# Top_Board_Boundary_Ref.net
KiCad netlist of a schematic drawn in EAGLE
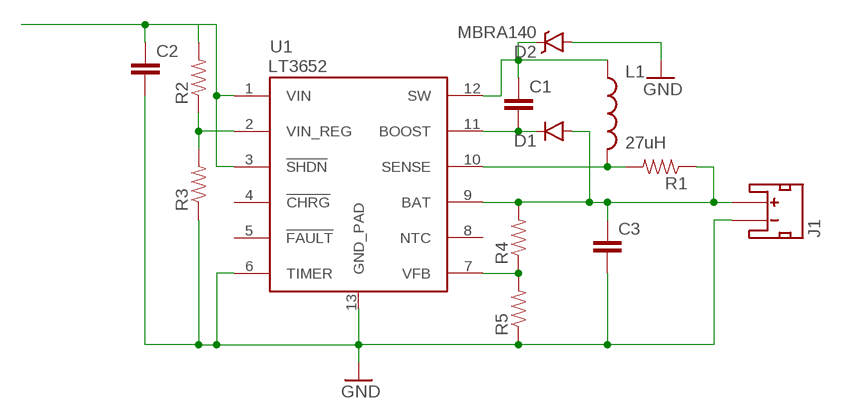
[diagram p0: schematic, sheet 1]

(export (version "E")
  (design (tool "Eeschema 10.0.6"))
  (components
    (comp (ref "C1")
      (value "CAP0805")
      (footprint "eagle-import:0805")
      (libsource (lib "eagle-import") (part "CAP0805"))
    )
    (comp (ref "C2")
      (value "CAP0805")
      (footprint "eagle-import:0805")
      (libsource (lib "eagle-import") (part "CAP0805"))
    )
    (comp (ref "C3")
      (value "CAP0805")
      (footprint "eagle-import:0805")
      (libsource (lib "eagle-import") (part "CAP0805"))
    )
    (comp (ref "D1")
      (value "DIODESMA")
      (footprint "eagle-import:SMA-DIODE")
      (libsource (lib "eagle-import") (part "DIODESMA"))
    )
    (comp (ref "D2")
      (value "MBRA140")
      (footprint "eagle-import:SMA-DIODE")
      (libsource (lib "eagle-import") (part "DIODE-SCHOTTKY-MBRA140"))
    )
    (comp (ref "J1")
      (value "JST_2MM_MALE")
      (footprint "eagle-import:JST-2-SMD")
      (libsource (lib "eagle-import") (part "JST_2MM_MALE"))
    )
    (comp (ref "L1")
      (value "27uH")
      (footprint "eagle-import:INDUCTOR_SDR1307")
      (libsource (lib "eagle-import") (part "INDUCTORSDR13-7-270ML"))
    )
    (comp (ref "R1")
      (value "RESISTOR0805-RES")
      (footprint "eagle-import:0805")
      (libsource (lib "eagle-import") (part "RESISTOR0805-RES"))
    )
    (comp (ref "R2")
      (value "RESISTOR0805-RES")
      (footprint "eagle-import:0805")
      (libsource (lib "eagle-import") (part "RESISTOR0805-RES"))
    )
    (comp (ref "R3")
      (value "RESISTOR0805-RES")
      (footprint "eagle-import:0805")
      (libsource (lib "eagle-import") (part "RESISTOR0805-RES"))
    )
    (comp (ref "R4")
      (value "RESISTOR0805-RES")
      (footprint "eagle-import:0805")
      (libsource (lib "eagle-import") (part "RESISTOR0805-RES"))
    )
    (comp (ref "R5")
      (value "RESISTOR0805-RES")
      (footprint "eagle-import:0805")
      (libsource (lib "eagle-import") (part "RESISTOR0805-RES"))
    )
    (comp (ref "U1")
      (value "LT3652")
      (footprint "eagle-import:MSOP-12_GND")
      (libsource (lib "eagle-import") (part "LT3652"))
    )
  )
  (nets
    (net (code "1") (name "GND") (class "Default")
      (node (ref "C2") (pin "2") (pinfunction "2_2") (pintype "passive"))
      (node (ref "C3") (pin "2") (pinfunction "2_2") (pintype "passive"))
      (node (ref "D2") (pin "A") (pinfunction "A_A") (pintype "passive"))
      (node (ref "J1") (pin "1") (pinfunction "-_1") (pintype "bidirectional"))
      (node (ref "R3") (pin "1") (pinfunction "1_1") (pintype "passive"))
      (node (ref "R5") (pin "1") (pinfunction "1_1") (pintype "passive"))
      (node (ref "U1") (pin "13") (pinfunction "GND_PAD_13") (pintype "bidirectional"))
      (node (ref "U1") (pin "6") (pinfunction "TIMER_6") (pintype "bidirectional"))
    )
    (net (code "2") (name "Net-(J1-+)") (class "Default")
      (node (ref "C3") (pin "1") (pinfunction "1_1") (pintype "passive"))
      (node (ref "D1") (pin "A") (pinfunction "A_A") (pintype "passive"))
      (node (ref "J1") (pin "2") (pinfunction "+_2") (pintype "bidirectional"))
      (node (ref "R1") (pin "1") (pinfunction "1_1") (pintype "passive"))
      (node (ref "R4") (pin "2") (pinfunction "2_2") (pintype "passive"))
      (node (ref "U1") (pin "9") (pinfunction "BAT_9") (pintype "bidirectional"))
    )
    (net (code "3") (name "Net-(L1-1)") (class "Default")
      (node (ref "C1") (pin "1") (pinfunction "1_1") (pintype "passive"))
      (node (ref "D2") (pin "C") (pinfunction "C_C") (pintype "passive"))
      (node (ref "L1") (pin "P$1") (pinfunction "1_P$1") (pintype "passive"))
      (node (ref "U1") (pin "12") (pinfunction "SW_12") (pintype "bidirectional"))
    )
    (net (code "4") (name "Net-(L1-2)") (class "Default")
      (node (ref "L1") (pin "P$2") (pinfunction "2_P$2") (pintype "passive"))
      (node (ref "R1") (pin "2") (pinfunction "2_2") (pintype "passive"))
      (node (ref "U1") (pin "10") (pinfunction "SENSE_10") (pintype "bidirectional"))
    )
    (net (code "5") (name "Net-(U1-BOOST)") (class "Default")
      (node (ref "C1") (pin "2") (pinfunction "2_2") (pintype "passive"))
      (node (ref "D1") (pin "C") (pinfunction "C_C") (pintype "passive"))
      (node (ref "U1") (pin "11") (pinfunction "BOOST_11") (pintype "bidirectional"))
    )
    (net (code "6") (name "Net-(U1-VFB)") (class "Default")
      (node (ref "R4") (pin "1") (pinfunction "1_1") (pintype "passive"))
      (node (ref "R5") (pin "2") (pinfunction "2_2") (pintype "passive"))
      (node (ref "U1") (pin "7") (pinfunction "VFB_7") (pintype "bidirectional"))
    )
    (net (code "7") (name "Net-(U1-VIN)") (class "Default")
      (node (ref "C2") (pin "1") (pinfunction "1_1") (pintype "passive"))
      (node (ref "R2") (pin "2") (pinfunction "2_2") (pintype "passive"))
      (node (ref "U1") (pin "1") (pinfunction "VIN_1") (pintype "bidirectional"))
      (node (ref "U1") (pin "3") (pinfunction "~{SHDN}_3") (pintype "bidirectional"))
    )
    (net (code "8") (name "Net-(U1-VIN_REG)") (class "Default")
      (node (ref "R2") (pin "1") (pinfunction "1_1") (pintype "passive"))
      (node (ref "R3") (pin "2") (pinfunction "2_2") (pintype "passive"))
      (node (ref "U1") (pin "2") (pinfunction "VIN_REG_2") (pintype "bidirectional"))
    )
    (net (code "9") (name "unconnected-(J1-PAD1-PadNC1)") (class "Default")
      (node (ref "J1") (pin "NC1") (pinfunction "PAD1_NC1") (pintype "bidirectional"))
    )
    (net (code "10") (name "unconnected-(J1-PAD2-PadNC2)") (class "Default")
      (node (ref "J1") (pin "NC2") (pinfunction "PAD2_NC2") (pintype "bidirectional"))
    )
    (net (code "11") (name "unconnected-(U1-NTC-Pad8)") (class "Default")
      (node (ref "U1") (pin "8") (pinfunction "NTC_8") (pintype "bidirectional"))
    )
    (net (code "12") (name "unconnected-(U1-~{CHRG}-Pad4)") (class "Default")
      (node (ref "U1") (pin "4") (pinfunction "~{CHRG}_4") (pintype "bidirectional"))
    )
    (net (code "13") (name "unconnected-(U1-~{FAULT}-Pad5)") (class "Default")
      (node (ref "U1") (pin "5") (pinfunction "~{FAULT}_5") (pintype "bidirectional"))
    )
  )
)
